# 18_RemoteSenseAmp.net
KiCad netlist of a schematic drawn in Altium Designer
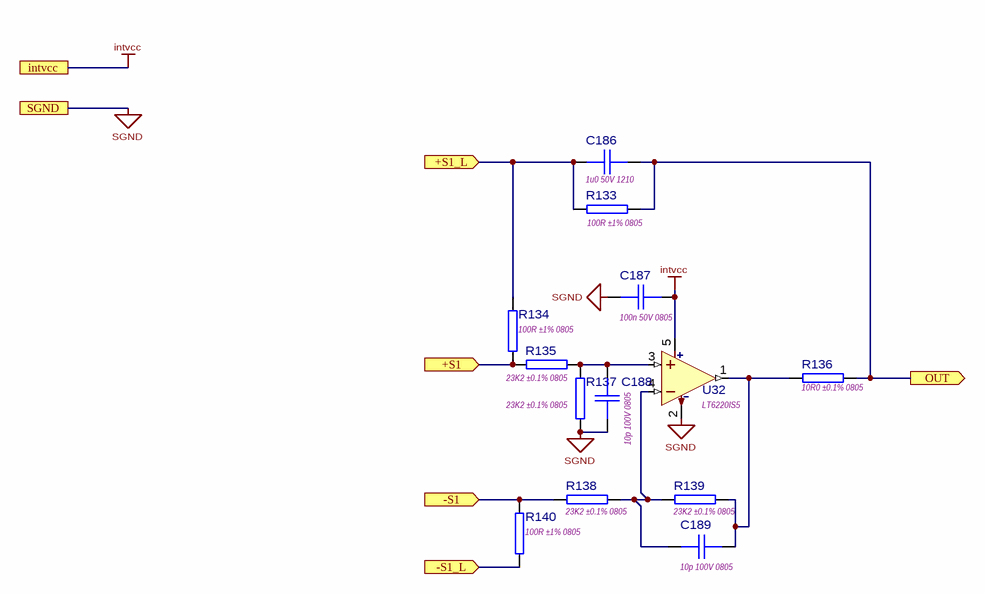
[diagram p0: [18] RemoteSenseAmp.SchDoc]

(export (version "E")
  (design (tool "Eeschema 10.0.6"))
  (components
    (comp (ref "C186")
      (value "1u0 50V 1210")
      (footprint "CAPC3225X200N")
      (description "1u0 50V X7R ±10% 1210 (3225 metric)")
      (fields (field (name "TOLERANCE") "10%") (field (name "PARTNUMBER") "GRM32RR71H105KA01"))
      (libsource (lib "Omnisys Vault") (part "CAP-2PIN"))
    )
    (comp (ref "C187")
      (value "100n 50V 0805")
      (footprint "CAPC2012X135N")
      (description "100n 50V X7R ±10% 0805 (2012 metric)")
      (fields (field (name "TOLERANCE") "10%") (field (name "PARTNUMBER") "GRM21BR71H104KA01"))
      (libsource (lib "Omnisys Vault") (part "CAP-2PIN"))
    )
    (comp (ref "C188")
      (value "10p 100V 0805")
      (footprint "CAPC2012X95N")
      (description "10p 100V 0805 CH +/-5% 0805 (2012 metric)")
      (fields (field (name "TOLERANCE") "5%") (field (name "PARTNUMBER") "GQM2192C2A100JB01"))
      (libsource (lib "Omnisys Vault") (part "CAP-2PIN"))
    )
    (comp (ref "C189")
      (value "10p 100V 0805")
      (footprint "CAPC2012X95N")
      (description "10p 100V 0805 CH +/-5% 0805 (2012 metric)")
      (fields (field (name "TOLERANCE") "5%") (field (name "PARTNUMBER") "GQM2192C2A100JB01"))
      (libsource (lib "Omnisys Vault") (part "CAP-2PIN"))
    )
    (comp (ref "R133")
      (value "100R ±1% 0805")
      (footprint "RESC2012N")
      (description "100R ±1% ±100 ppm/˚C 0.125W 150V 0805 (2012 metric)")
      (fields (field (name "TOLERANCE") "1%") (field (name "POWER") "125mW"))
      (libsource (lib "Omnisys Vault") (part "RES-2PIN"))
    )
    (comp (ref "R134")
      (value "100R ±1% 0805")
      (footprint "RESC2012N")
      (description "100R ±1% ±100 ppm/˚C 0.125W 150V 0805 (2012 metric)")
      (fields (field (name "TOLERANCE") "1%") (field (name "POWER") "125mW"))
      (libsource (lib "Omnisys Vault") (part "RES-2PIN"))
    )
    (comp (ref "R135")
      (value "23K2 ±0.1% 0805")
      (footprint "RESC2012N")
      (description "23K2 ±0.1% ±10 ppm/˚C 0.1W 100V 0805 (2012 metric) Thinfilm")
      (fields (field (name "POWER") "0.1W") (field (name "TOLERANCE") "±0.1"))
      (libsource (lib "Omnisys Vault") (part "RES-2PIN"))
    )
    (comp (ref "R136")
      (value "10R0 ±0.1% 0805")
      (footprint "RESC2012N")
      (description "10R0 ±0.1% ±10 ppm/˚C 0.1W 100V 0805 (2012 metric) Thinfilm")
      (fields (field (name "TOLERANCE") "±0.1") (field (name "POWER") "0.1W"))
      (libsource (lib "Omnisys Vault") (part "RES-2PIN"))
    )
    (comp (ref "R137")
      (value "23K2 ±0.1% 0805")
      (footprint "RESC2012N")
      (description "23K2 ±0.1% ±10 ppm/˚C 0.1W 100V 0805 (2012 metric) Thinfilm")
      (fields (field (name "POWER") "0.1W") (field (name "TOLERANCE") "±0.1"))
      (libsource (lib "Omnisys Vault") (part "RES-2PIN"))
    )
    (comp (ref "R138")
      (value "23K2 ±0.1% 0805")
      (footprint "RESC2012N")
      (description "23K2 ±0.1% ±10 ppm/˚C 0.1W 100V 0805 (2012 metric) Thinfilm")
      (fields (field (name "POWER") "0.1W") (field (name "TOLERANCE") "±0.1"))
      (libsource (lib "Omnisys Vault") (part "RES-2PIN"))
    )
    (comp (ref "R139")
      (value "23K2 ±0.1% 0805")
      (footprint "RESC2012N")
      (description "23K2 ±0.1% ±10 ppm/˚C 0.1W 100V 0805 (2012 metric) Thinfilm")
      (fields (field (name "POWER") "0.1W") (field (name "TOLERANCE") "±0.1"))
      (libsource (lib "Omnisys Vault") (part "RES-2PIN"))
    )
    (comp (ref "R140")
      (value "100R ±1% 0805")
      (footprint "RESC2012N")
      (description "100R ±1% ±100 ppm/˚C 0.125W 150V 0805 (2012 metric)")
      (fields (field (name "TOLERANCE") "1%") (field (name "POWER") "125mW"))
      (libsource (lib "Omnisys Vault") (part "RES-2PIN"))
    )
    (comp (ref "U32")
      (value "LT6220IS5")
      (footprint "SOT95P280X100-5N")
      (description "60MHz, 20V/µs, Low Power, Rail-to-Rail Input and Output")
      (fields (field (name "PARTNUMBER") "LT6220IS5#TRMPBF"))
      (libsource (lib "Omnisys Vault") (part "OPAMP-SOT23-5"))
    )
  )
  (nets
    (net (code "1") (name "/+S1") (class "Default")
      (node (ref "R134") (pin "1") (pinfunction "1_1") (pintype "passive"))
      (node (ref "R135") (pin "1") (pinfunction "1_1") (pintype "passive"))
    )
    (net (code "2") (name "/+S1_L") (class "Default")
      (node (ref "C186") (pin "1") (pinfunction "1_1") (pintype "passive"))
      (node (ref "R133") (pin "2") (pinfunction "2_2") (pintype "passive"))
      (node (ref "R134") (pin "2") (pinfunction "2_2") (pintype "passive"))
    )
    (net (code "3") (name "/-S1") (class "Default")
      (node (ref "R138") (pin "1") (pinfunction "1_1") (pintype "passive"))
      (node (ref "R140") (pin "2") (pinfunction "2_2") (pintype "passive"))
    )
    (net (code "4") (name "/-S1_L") (class "Default")
      (node (ref "R140") (pin "1") (pinfunction "1_1") (pintype "passive"))
    )
    (net (code "5") (name "/OUT") (class "Default")
      (node (ref "C186") (pin "2") (pinfunction "2_2") (pintype "passive"))
      (node (ref "R133") (pin "1") (pinfunction "1_1") (pintype "passive"))
      (node (ref "R136") (pin "1") (pinfunction "1_1") (pintype "passive"))
    )
    (net (code "6") (name "Net-(U32-+IN)") (class "Default")
      (node (ref "C188") (pin "2") (pinfunction "2_2") (pintype "passive"))
      (node (ref "R135") (pin "2") (pinfunction "2_2") (pintype "passive"))
      (node (ref "R137") (pin "2") (pinfunction "2_2") (pintype "passive"))
      (node (ref "U32") (pin "3") (pinfunction "+IN_3") (pintype "input"))
    )
    (net (code "7") (name "Net-(U32--IN)") (class "Default")
      (node (ref "C189") (pin "2") (pinfunction "2_2") (pintype "passive"))
      (node (ref "R138") (pin "2") (pinfunction "2_2") (pintype "passive"))
      (node (ref "R139") (pin "1") (pinfunction "1_1") (pintype "passive"))
      (node (ref "U32") (pin "4") (pinfunction "-IN_4") (pintype "input"))
    )
    (net (code "8") (name "Net-(U32-OUT)") (class "Default")
      (node (ref "C189") (pin "1") (pinfunction "1_1") (pintype "passive"))
      (node (ref "R136") (pin "2") (pinfunction "2_2") (pintype "passive"))
      (node (ref "R139") (pin "2") (pinfunction "2_2") (pintype "passive"))
      (node (ref "U32") (pin "1") (pinfunction "OUT_1") (pintype "output"))
    )
    (net (code "9") (name "SGND") (class "Default")
      (node (ref "C187") (pin "1") (pinfunction "1_1") (pintype "passive"))
      (node (ref "C188") (pin "1") (pinfunction "1_1") (pintype "passive"))
      (node (ref "R137") (pin "1") (pinfunction "1_1") (pintype "passive"))
      (node (ref "U32") (pin "2") (pinfunction "-V_2") (pintype "power_in"))
    )
    (net (code "10") (name "intvcc") (class "Default")
      (node (ref "C187") (pin "2") (pinfunction "2_2") (pintype "passive"))
      (node (ref "U32") (pin "5") (pinfunction "+V_5") (pintype "power_in"))
    )
  )
)
